# ESP_CAM_VVN_v5.net
KiCad netlist of a schematic drawn in EAGLE
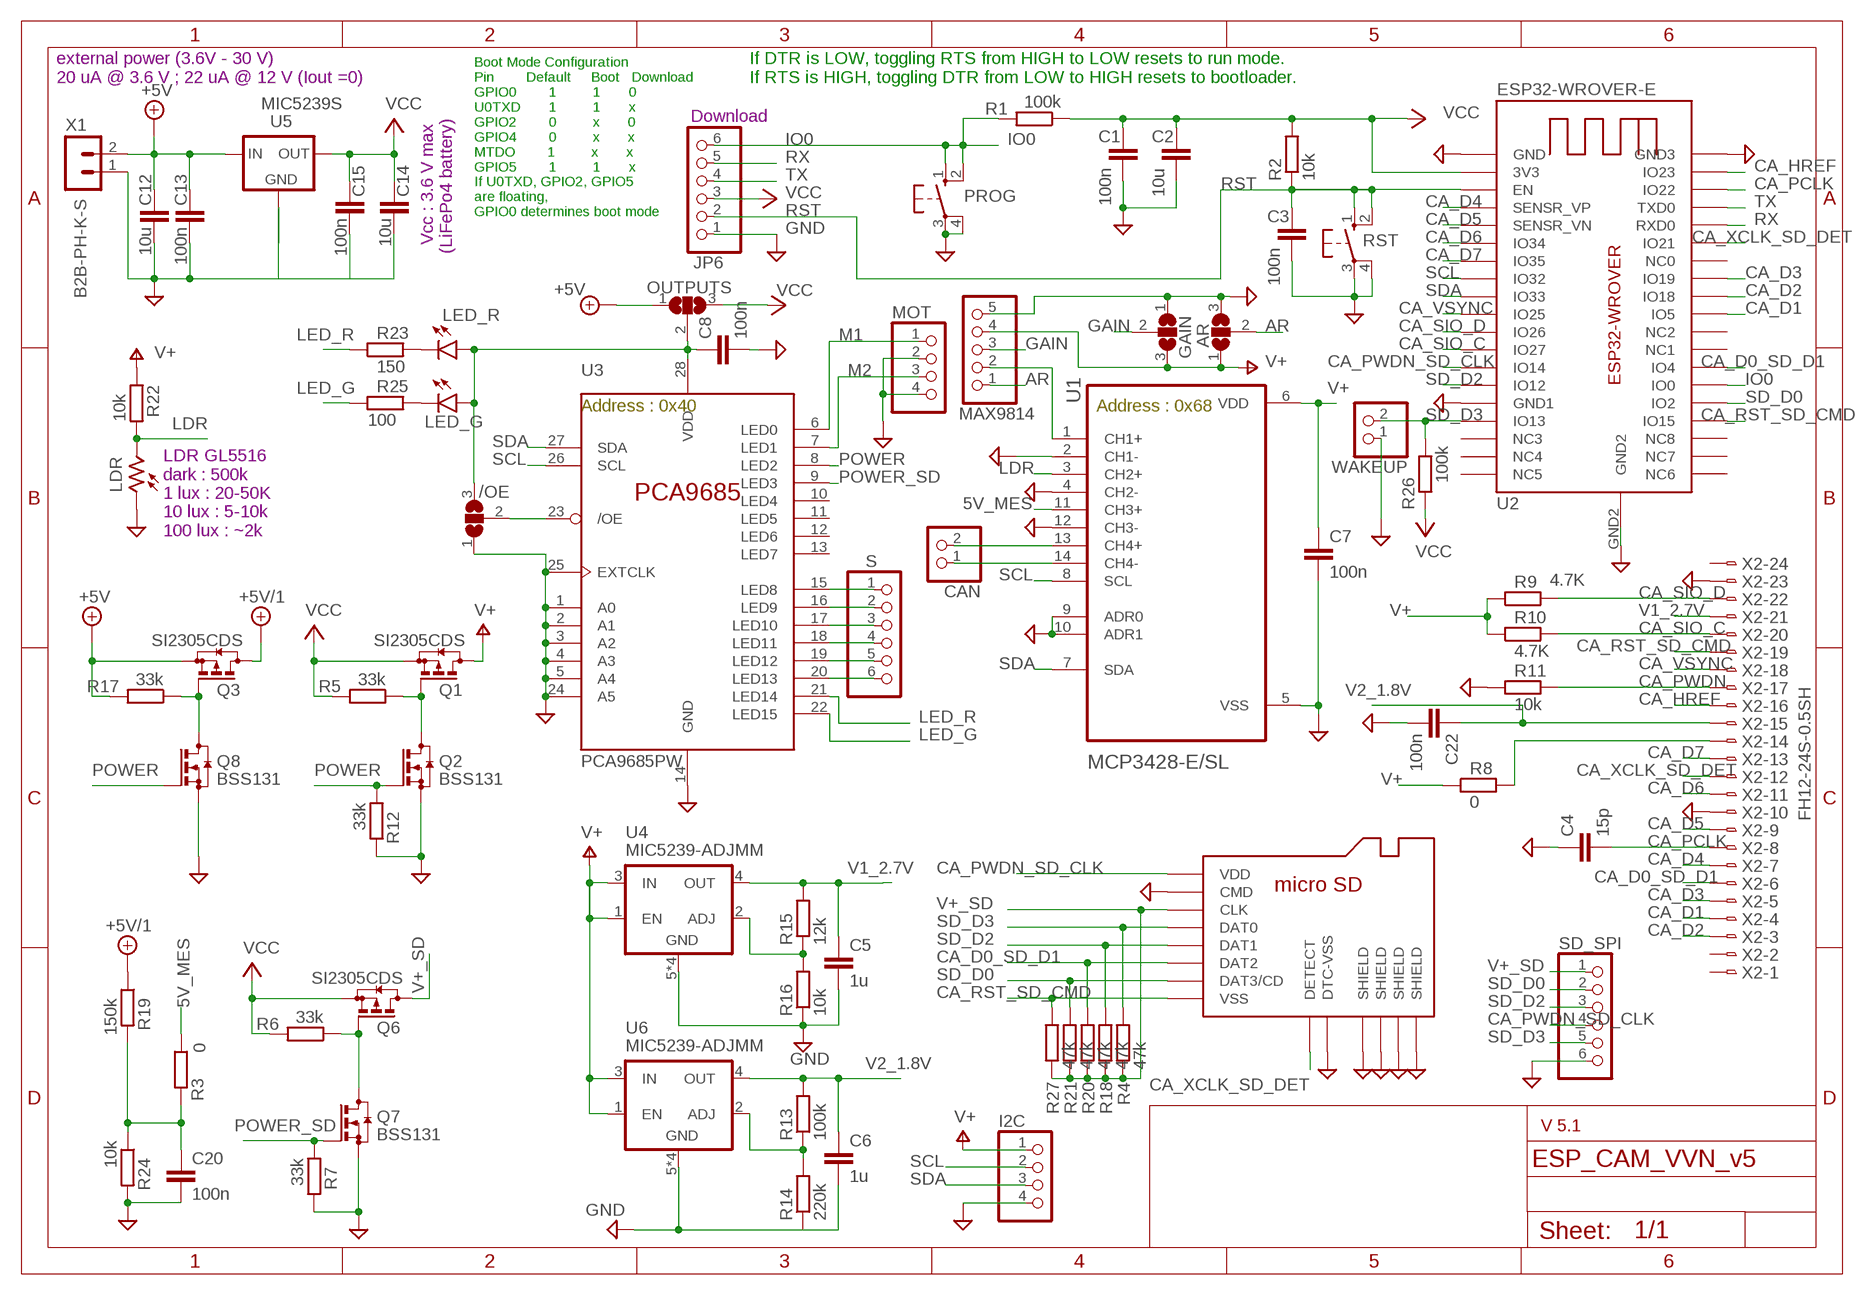
[diagram p0: schematic, sheet 1]

(export (version "E")
  (design (tool "Eeschema 10.0.6"))
  (components
    (comp (ref "/OE")
      (value "SJ2W")
      (footprint "eagle-import:SJ_2")
      (libsource (lib "eagle-import") (part "SJ2W"))
    )
    (comp (ref "AR")
      (value "SJ2W")
      (footprint "eagle-import:SJ_2")
      (libsource (lib "eagle-import") (part "SJ2W"))
    )
    (comp (ref "C1")
      (value "100n")
      (footprint "eagle-import:C1206")
      (libsource (lib "eagle-import") (part "CC1206"))
    )
    (comp (ref "C2")
      (value "10u")
      (footprint "eagle-import:C1206")
      (libsource (lib "eagle-import") (part "CC1206"))
    )
    (comp (ref "C3")
      (value "100n")
      (footprint "eagle-import:C1206")
      (libsource (lib "eagle-import") (part "CC1206"))
    )
    (comp (ref "C4")
      (value "15p")
      (footprint "eagle-import:C1206")
      (libsource (lib "eagle-import") (part "CC1206"))
    )
    (comp (ref "C5")
      (value "1u")
      (footprint "eagle-import:C1206")
      (libsource (lib "eagle-import") (part "C-EUC1206"))
    )
    (comp (ref "C6")
      (value "1u")
      (footprint "eagle-import:C1206")
      (libsource (lib "eagle-import") (part "C-EUC1206"))
    )
    (comp (ref "C7")
      (value "100n")
      (footprint "eagle-import:C1206")
      (libsource (lib "eagle-import") (part "CC1206"))
    )
    (comp (ref "C8")
      (value "100n")
      (footprint "eagle-import:C1206")
      (libsource (lib "eagle-import") (part "CC1206"))
    )
    (comp (ref "C12")
      (value "10u")
      (footprint "eagle-import:C1206")
      (libsource (lib "eagle-import") (part "CC1206"))
    )
    (comp (ref "C13")
      (value "100n")
      (footprint "eagle-import:C1206")
      (libsource (lib "eagle-import") (part "CC1206"))
    )
    (comp (ref "C14")
      (value "10u")
      (footprint "eagle-import:C1206")
      (libsource (lib "eagle-import") (part "CC1206"))
    )
    (comp (ref "C15")
      (value "100n")
      (footprint "eagle-import:C1206")
      (libsource (lib "eagle-import") (part "CC1206"))
    )
    (comp (ref "C20")
      (value "100n")
      (footprint "eagle-import:C1206")
      (libsource (lib "eagle-import") (part "CC1206"))
    )
    (comp (ref "C22")
      (value "100n")
      (footprint "eagle-import:C1206")
      (libsource (lib "eagle-import") (part "CC1206"))
    )
    (comp (ref "CAN")
      (value "PINHD-1X2")
      (footprint "eagle-import:1X02")
      (libsource (lib "eagle-import") (part "PINHD-1X2"))
    )
    (comp (ref "GAIN")
      (value "SJ2W")
      (footprint "eagle-import:SJ_2")
      (libsource (lib "eagle-import") (part "SJ2W"))
    )
    (comp (ref "I2C")
      (value "PINHD-1X4")
      (footprint "eagle-import:1X04")
      (libsource (lib "eagle-import") (part "PINHD-1X4"))
    )
    (comp (ref "JP6")
      (value "PINHD-1X6/90")
      (footprint "eagle-import:1X06_90")
      (libsource (lib "eagle-import") (part "PINHD-1X6/90"))
    )
    (comp (ref "LDR")
      (value "VT93N2")
      (footprint "eagle-import:VT900")
      (libsource (lib "eagle-import") (part "VT93N2"))
    )
    (comp (ref "LED_G")
      (value "LEDSMT1206")
      (footprint "eagle-import:1206")
      (libsource (lib "eagle-import") (part "LEDSMT1206"))
    )
    (comp (ref "LED_R")
      (value "LEDSMT1206")
      (footprint "eagle-import:1206")
      (libsource (lib "eagle-import") (part "LEDSMT1206"))
    )
    (comp (ref "MAX9814")
      (value "PINHD-1X5")
      (footprint "eagle-import:1X05")
      (libsource (lib "eagle-import") (part "PINHD-1X5"))
    )
    (comp (ref "MOT")
      (value "PINHD-1X4")
      (footprint "eagle-import:1X04")
      (libsource (lib "eagle-import") (part "PINHD-1X4"))
    )
    (comp (ref "OUTPUTS")
      (value "SJ2W")
      (footprint "eagle-import:SJ_2")
      (libsource (lib "eagle-import") (part "SJ2W"))
    )
    (comp (ref "PROG")
      (value "10-XX")
      (footprint "eagle-import:B3F-10XX")
      (fields (field (name "MPN") "B3F-1000"))
      (libsource (lib "eagle-import") (part "10-XX"))
    )
    (comp (ref "Q1")
      (value "SI2305CDS")
      (footprint "eagle-import:SOT23")
      (libsource (lib "eagle-import") (part "SI2305CDS"))
    )
    (comp (ref "Q2")
      (value "BSS131")
      (footprint "eagle-import:SOT23")
      (libsource (lib "eagle-import") (part "BSS131"))
    )
    (comp (ref "Q3")
      (value "SI2305CDS")
      (footprint "eagle-import:SOT23")
      (libsource (lib "eagle-import") (part "SI2305CDS"))
    )
    (comp (ref "Q6")
      (value "SI2305CDS")
      (footprint "eagle-import:SOT23")
      (libsource (lib "eagle-import") (part "SI2305CDS"))
    )
    (comp (ref "Q7")
      (value "BSS131")
      (footprint "eagle-import:SOT23")
      (libsource (lib "eagle-import") (part "BSS131"))
    )
    (comp (ref "Q8")
      (value "BSS131")
      (footprint "eagle-import:SOT23")
      (libsource (lib "eagle-import") (part "BSS131"))
    )
    (comp (ref "R1")
      (value "100k")
      (footprint "eagle-import:R1206")
      (libsource (lib "eagle-import") (part "RR1206"))
    )
    (comp (ref "R2")
      (value "10k")
      (footprint "eagle-import:R1206")
      (libsource (lib "eagle-import") (part "RR1206"))
    )
    (comp (ref "R3")
      (value "0")
      (footprint "eagle-import:R1206")
      (libsource (lib "eagle-import") (part "RR1206"))
    )
    (comp (ref "R4")
      (value "47k")
      (footprint "eagle-import:R0805")
      (libsource (lib "eagle-import") (part "R-EU_R0805"))
    )
    (comp (ref "R5")
      (value "33k")
      (footprint "eagle-import:R1206")
      (libsource (lib "eagle-import") (part "RR1206"))
    )
    (comp (ref "R6")
      (value "33k")
      (footprint "eagle-import:R1206")
      (libsource (lib "eagle-import") (part "RR1206"))
    )
    (comp (ref "R7")
      (value "33k")
      (footprint "eagle-import:R1206")
      (libsource (lib "eagle-import") (part "RR1206"))
    )
    (comp (ref "R8")
      (value "0")
      (footprint "eagle-import:R1206")
      (libsource (lib "eagle-import") (part "RR1206"))
    )
    (comp (ref "R9")
      (value "4.7K")
      (footprint "eagle-import:R1206")
      (libsource (lib "eagle-import") (part "RR1206"))
    )
    (comp (ref "R10")
      (value "4.7K")
      (footprint "eagle-import:R1206")
      (libsource (lib "eagle-import") (part "RR1206"))
    )
    (comp (ref "R11")
      (value "10k")
      (footprint "eagle-import:R1206")
      (libsource (lib "eagle-import") (part "RR1206"))
    )
    (comp (ref "R12")
      (value "33k")
      (footprint "eagle-import:R1206")
      (libsource (lib "eagle-import") (part "RR1206"))
    )
    (comp (ref "R13")
      (value "100k")
      (footprint "eagle-import:R1206")
      (libsource (lib "eagle-import") (part "R-EU_R1206"))
    )
    (comp (ref "R14")
      (value "220k")
      (footprint "eagle-import:R1206")
      (libsource (lib "eagle-import") (part "R-EU_R1206"))
    )
    (comp (ref "R15")
      (value "12k")
      (footprint "eagle-import:R1206")
      (libsource (lib "eagle-import") (part "R-EU_R1206"))
    )
    (comp (ref "R16")
      (value "10k")
      (footprint "eagle-import:R1206")
      (libsource (lib "eagle-import") (part "R-EU_R1206"))
    )
    (comp (ref "R17")
      (value "33k")
      (footprint "eagle-import:R1206")
      (libsource (lib "eagle-import") (part "RR1206"))
    )
    (comp (ref "R18")
      (value "47k")
      (footprint "eagle-import:R0805")
      (libsource (lib "eagle-import") (part "R-EU_R0805"))
    )
    (comp (ref "R19")
      (value "150k")
      (footprint "eagle-import:R1206")
      (libsource (lib "eagle-import") (part "RR1206"))
    )
    (comp (ref "R20")
      (value "47k")
      (footprint "eagle-import:R0805")
      (libsource (lib "eagle-import") (part "R-EU_R0805"))
    )
    (comp (ref "R21")
      (value "47k")
      (footprint "eagle-import:R0805")
      (libsource (lib "eagle-import") (part "R-EU_R0805"))
    )
    (comp (ref "R22")
      (value "10k")
      (footprint "eagle-import:R1206")
      (libsource (lib "eagle-import") (part "RR1206"))
    )
    (comp (ref "R23")
      (value "150")
      (footprint "eagle-import:R1206")
      (libsource (lib "eagle-import") (part "RR1206"))
    )
    (comp (ref "R24")
      (value "10k")
      (footprint "eagle-import:R1206")
      (libsource (lib "eagle-import") (part "RR1206"))
    )
    (comp (ref "R25")
      (value "100")
      (footprint "eagle-import:R1206")
      (libsource (lib "eagle-import") (part "RR1206"))
    )
    (comp (ref "R26")
      (value "100k")
      (footprint "eagle-import:R1206")
      (libsource (lib "eagle-import") (part "RR1206"))
    )
    (comp (ref "R27")
      (value "47k")
      (footprint "eagle-import:R0805")
      (libsource (lib "eagle-import") (part "R-EU_R0805"))
    )
    (comp (ref "RST")
      (value "10-XX")
      (footprint "eagle-import:B3F-10XX")
      (fields (field (name "MPN") "B3F-1000"))
      (libsource (lib "eagle-import") (part "10-XX"))
    )
    (comp (ref "S")
      (value "PINHD-1X6")
      (footprint "eagle-import:1X06")
      (libsource (lib "eagle-import") (part "PINHD-1X6"))
    )
    (comp (ref "SD1")
      (value "MICRO-SD-8")
      (footprint "eagle-import:MICROSDMOLEX")
      (libsource (lib "eagle-import") (part "MICRO-SD-8"))
    )
    (comp (ref "SD_SPI")
      (value "PINHD-1X6")
      (footprint "eagle-import:1X06")
      (libsource (lib "eagle-import") (part "PINHD-1X6"))
    )
    (comp (ref "U1")
      (value "MCP3428-E/SL")
      (footprint "eagle-import:SOIC127P600X175-14N")
      (fields (field (name "MF") "Microchip"))
      (libsource (lib "eagle-import") (part "MCP3428-E/SL"))
    )
    (comp (ref "U2")
      (value "ESP32-WROVER-E")
      (footprint "eagle-import:ESP32-WROVER")
      (libsource (lib "eagle-import") (part "ESP32-WROVER-E"))
    )
    (comp (ref "U3")
      (value "PCA9685PW")
      (footprint "eagle-import:TSSOP28")
      (libsource (lib "eagle-import") (part "PCA9685PW"))
    )
    (comp (ref "U4")
      (value "MIC5239-ADJMM")
      (footprint "eagle-import:MSOP08")
      (libsource (lib "eagle-import") (part "MIC5239-ADJMM"))
    )
    (comp (ref "U5")
      (value "MIC5239S")
      (footprint "eagle-import:SOT223")
      (libsource (lib "eagle-import") (part "MIC5239S"))
    )
    (comp (ref "U6")
      (value "MIC5239-ADJMM")
      (footprint "eagle-import:MSOP08")
      (libsource (lib "eagle-import") (part "MIC5239-ADJMM"))
    )
    (comp (ref "WAKEUP")
      (value "PINHD-1X2")
      (footprint "eagle-import:1X02")
      (libsource (lib "eagle-import") (part "PINHD-1X2"))
    )
    (comp (ref "X1")
      (value "B2B-PH-K-S")
      (footprint "eagle-import:B2B-PH-K-S")
      (libsource (lib "eagle-import") (part "B2B-PH-K-S"))
    )
    (comp (ref "X2")
      (value "FH12-24S-0.5SH")
      (footprint "eagle-import:FH12-24S-0.5SH")
      (fields (field (name "MPN") "FH12-24S-0.5SH(55)"))
      (libsource (lib "eagle-import") (part "FH12-24S-0.5SH"))
    )
  )
  (nets
    (net (code "1") (name "+5V") (class "Default")
      (node (ref "C12") (pin "1") (pinfunction "1_1") (pintype "passive"))
      (node (ref "C13") (pin "1") (pinfunction "1_1") (pintype "passive"))
      (node (ref "OUTPUTS") (pin "1") (pinfunction "1_1") (pintype "passive"))
      (node (ref "Q3") (pin "2") (pinfunction "S_2") (pintype "passive"))
      (node (ref "R17") (pin "2") (pinfunction "2_2") (pintype "passive"))
      (node (ref "U5") (pin "1") (pinfunction "IN_1") (pintype "input"))
      (node (ref "X1") (pin "2") (pinfunction "2_2") (pintype "passive"))
    )
    (net (code "2") (name "+5V{slash}1") (class "Default")
      (node (ref "Q3") (pin "3") (pinfunction "D_3") (pintype "passive"))
      (node (ref "R19") (pin "1") (pinfunction "1_1") (pintype "passive"))
    )
    (net (code "3") (name "/5V_MES") (class "Default")
      (node (ref "R3") (pin "1") (pinfunction "1_1") (pintype "passive"))
      (node (ref "U1") (pin "11") (pinfunction "CH3+_11") (pintype "input"))
    )
    (net (code "4") (name "/AR") (class "Default")
      (node (ref "AR") (pin "2") (pinfunction "2_2") (pintype "passive"))
      (node (ref "MAX9814") (pin "1") (pinfunction "1_1") (pintype "passive"))
    )
    (net (code "5") (name "/CA_D0_SD_D1") (class "Default")
      (node (ref "R20") (pin "2") (pinfunction "2_2") (pintype "passive"))
      (node (ref "SD1") (pin "P$1") (pinfunction "DAT2_P$1") (pintype "bidirectional"))
      (node (ref "U2") (pin "IO4") (pinfunction "IO4_IO4") (pintype "bidirectional"))
      (node (ref "X2") (pin "6") (pinfunction "1_6") (pintype "passive"))
    )
    (net (code "6") (name "/CA_D1") (class "Default")
      (node (ref "U2") (pin "IO5") (pinfunction "IO5_IO5") (pintype "bidirectional"))
      (node (ref "X2") (pin "4") (pinfunction "1_4") (pintype "passive"))
    )
    (net (code "7") (name "/CA_D2") (class "Default")
      (node (ref "U2") (pin "IO18") (pinfunction "IO18_IO18") (pintype "bidirectional"))
      (node (ref "X2") (pin "3") (pinfunction "1_3") (pintype "passive"))
    )
    (net (code "8") (name "/CA_D3") (class "Default")
      (node (ref "U2") (pin "IO19") (pinfunction "IO19_IO19") (pintype "bidirectional"))
      (node (ref "X2") (pin "5") (pinfunction "1_5") (pintype "passive"))
    )
    (net (code "9") (name "/CA_D4") (class "Default")
      (node (ref "U2") (pin "SENSOR_VP") (pinfunction "SENSR_VP_SENSOR_VP") (pintype "bidirectional"))
      (node (ref "X2") (pin "7") (pinfunction "1_7") (pintype "passive"))
    )
    (net (code "10") (name "/CA_D5") (class "Default")
      (node (ref "U2") (pin "SENSOR_VN") (pinfunction "SENSR_VN_SENSOR_VN") (pintype "bidirectional"))
      (node (ref "X2") (pin "9") (pinfunction "1_9") (pintype "passive"))
    )
    (net (code "11") (name "/CA_D6") (class "Default")
      (node (ref "U2") (pin "IO34") (pinfunction "IO34_IO34") (pintype "bidirectional"))
      (node (ref "X2") (pin "11") (pinfunction "1_11") (pintype "passive"))
    )
    (net (code "12") (name "/CA_D7") (class "Default")
      (node (ref "U2") (pin "IO35") (pinfunction "IO35_IO35") (pintype "bidirectional"))
      (node (ref "X2") (pin "13") (pinfunction "1_13") (pintype "passive"))
    )
    (net (code "13") (name "/CA_HREF") (class "Default")
      (node (ref "U2") (pin "IO23") (pinfunction "IO23_IO23") (pintype "bidirectional"))
      (node (ref "X2") (pin "16") (pinfunction "1_16") (pintype "passive"))
    )
    (net (code "14") (name "/CA_PCLK") (class "Default")
      (node (ref "C4") (pin "2") (pinfunction "2_2") (pintype "passive"))
      (node (ref "U2") (pin "IO22") (pinfunction "IO22_IO22") (pintype "bidirectional"))
      (node (ref "X2") (pin "8") (pinfunction "1_8") (pintype "passive"))
    )
    (net (code "15") (name "/CA_PWDN") (class "Default")
      (node (ref "R11") (pin "2") (pinfunction "2_2") (pintype "passive"))
      (node (ref "X2") (pin "17") (pinfunction "1_17") (pintype "passive"))
    )
    (net (code "16") (name "/CA_PWDN_SD_CLK") (class "Default")
      (node (ref "SD1") (pin "P$4") (pinfunction "VDD_P$4") (pintype "power_in"))
      (node (ref "SD_SPI") (pin "4") (pinfunction "4_4") (pintype "passive"))
      (node (ref "U2") (pin "IO14") (pinfunction "IO14_IO14") (pintype "bidirectional"))
    )
    (net (code "17") (name "/CA_RST_SD_CMD") (class "Default")
      (node (ref "R27") (pin "2") (pinfunction "2_2") (pintype "passive"))
      (node (ref "SD1") (pin "P$6") (pinfunction "VSS_P$6") (pintype "power_in"))
      (node (ref "U2") (pin "IO15") (pinfunction "IO15_IO15") (pintype "bidirectional"))
      (node (ref "X2") (pin "19") (pinfunction "1_19") (pintype "passive"))
    )
    (net (code "18") (name "/CA_SIO_C") (class "Default")
      (node (ref "R10") (pin "2") (pinfunction "2_2") (pintype "passive"))
      (node (ref "U2") (pin "IO27") (pinfunction "IO27_IO27") (pintype "bidirectional"))
      (node (ref "X2") (pin "20") (pinfunction "1_20") (pintype "passive"))
    )
    (net (code "19") (name "/CA_SIO_D") (class "Default")
      (node (ref "R9") (pin "2") (pinfunction "2_2") (pintype "passive"))
      (node (ref "U2") (pin "IO26") (pinfunction "IO26_IO26") (pintype "bidirectional"))
      (node (ref "X2") (pin "22") (pinfunction "1_22") (pintype "passive"))
    )
    (net (code "20") (name "/CA_VSYNC") (class "Default")
      (node (ref "U2") (pin "IO25") (pinfunction "IO25_IO25") (pintype "bidirectional"))
      (node (ref "X2") (pin "18") (pinfunction "1_18") (pintype "passive"))
    )
    (net (code "21") (name "/CA_XCLK_SD_DET") (class "Default")
      (node (ref "SD1") (pin "P$14") (pinfunction "DETECT_P$14") (pintype "power_in"))
      (node (ref "U2") (pin "IO21") (pinfunction "IO21_IO21") (pintype "bidirectional"))
      (node (ref "X2") (pin "12") (pinfunction "1_12") (pintype "passive"))
    )
    (net (code "22") (name "/GAIN") (class "Default")
      (node (ref "GAIN") (pin "2") (pinfunction "2_2") (pintype "passive"))
      (node (ref "MAX9814") (pin "3") (pinfunction "3_3") (pintype "passive"))
    )
    (net (code "23") (name "/IO0") (class "Default")
      (node (ref "JP6") (pin "6") (pinfunction "6_6") (pintype "passive"))
      (node (ref "PROG") (pin "1") (pinfunction "S_1") (pintype "passive"))
      (node (ref "PROG") (pin "2") (pinfunction "S1_2") (pintype "passive"))
      (node (ref "R1") (pin "2") (pinfunction "2_2") (pintype "passive"))
      (node (ref "U2") (pin "IO0") (pinfunction "IO0_IO0") (pintype "bidirectional"))
    )
    (net (code "24") (name "/LDR") (class "Default")
      (node (ref "LDR") (pin "2") (pinfunction "2_2") (pintype "passive"))
      (node (ref "R22") (pin "2") (pinfunction "2_2") (pintype "passive"))
      (node (ref "U1") (pin "3") (pinfunction "CH2+_3") (pintype "input"))
    )
    (net (code "25") (name "/LED_G") (class "Default")
      (node (ref "R25") (pin "1") (pinfunction "1_1") (pintype "passive"))
      (node (ref "U3") (pin "22") (pinfunction "LED15_22") (pintype "bidirectional"))
    )
    (net (code "26") (name "/LED_R") (class "Default")
      (node (ref "R23") (pin "1") (pinfunction "1_1") (pintype "passive"))
      (node (ref "U3") (pin "21") (pinfunction "LED14_21") (pintype "bidirectional"))
    )
    (net (code "27") (name "/M1") (class "Default")
      (node (ref "MOT") (pin "1") (pinfunction "1_1") (pintype "passive"))
      (node (ref "U3") (pin "6") (pinfunction "LED0_6") (pintype "bidirectional"))
    )
    (net (code "28") (name "/M2") (class "Default")
      (node (ref "MOT") (pin "3") (pinfunction "3_3") (pintype "passive"))
      (node (ref "U3") (pin "7") (pinfunction "LED1_7") (pintype "bidirectional"))
    )
    (net (code "29") (name "/POWER") (class "Default")
      (node (ref "Q2") (pin "1") (pinfunction "G_1") (pintype "passive"))
      (node (ref "Q8") (pin "1") (pinfunction "G_1") (pintype "passive"))
      (node (ref "R12") (pin "1") (pinfunction "1_1") (pintype "passive"))
      (node (ref "U3") (pin "8") (pinfunction "LED2_8") (pintype "bidirectional"))
    )
    (net (code "30") (name "/POWER_SD") (class "Default")
      (node (ref "Q7") (pin "1") (pinfunction "G_1") (pintype "passive"))
      (node (ref "R7") (pin "1") (pinfunction "1_1") (pintype "passive"))
      (node (ref "U3") (pin "9") (pinfunction "LED3_9") (pintype "bidirectional"))
    )
    (net (code "31") (name "/RST") (class "Default")
      (node (ref "C3") (pin "1") (pinfunction "1_1") (pintype "passive"))
      (node (ref "JP6") (pin "2") (pinfunction "2_2") (pintype "passive"))
      (node (ref "R2") (pin "1") (pinfunction "1_1") (pintype "passive"))
      (node (ref "RST") (pin "1") (pinfunction "S_1") (pintype "passive"))
      (node (ref "RST") (pin "2") (pinfunction "S1_2") (pintype "passive"))
      (node (ref "U2") (pin "EN") (pinfunction "EN_EN") (pintype "bidirectional"))
    )
    (net (code "32") (name "/RX") (class "Default")
      (node (ref "JP6") (pin "5") (pinfunction "5_5") (pintype "passive"))
      (node (ref "U2") (pin "RXD0") (pinfunction "RXD0_RXD0") (pintype "bidirectional"))
    )
    (net (code "33") (name "/SCL") (class "Default")
      (node (ref "I2C") (pin "2") (pinfunction "2_2") (pintype "passive"))
      (node (ref "U1") (pin "8") (pinfunction "SCL_8") (pintype "input"))
      (node (ref "U2") (pin "IO32") (pinfunction "IO32_IO32") (pintype "bidirectional"))
      (node (ref "U3") (pin "26") (pinfunction "SCL_26") (pintype "bidirectional"))
    )
    (net (code "34") (name "/SDA") (class "Default")
      (node (ref "I2C") (pin "3") (pinfunction "3_3") (pintype "passive"))
      (node (ref "U1") (pin "7") (pinfunction "SDA_7") (pintype "bidirectional"))
      (node (ref "U2") (pin "IO33") (pinfunction "IO33_IO33") (pintype "bidirectional"))
      (node (ref "U3") (pin "27") (pinfunction "SDA_27") (pintype "bidirectional"))
    )
    (net (code "35") (name "/SD_D0") (class "Default")
      (node (ref "R21") (pin "2") (pinfunction "2_2") (pintype "passive"))
      (node (ref "SD1") (pin "P$2") (pinfunction "DAT3/CD_P$2") (pintype "bidirectional"))
      (node (ref "SD_SPI") (pin "2") (pinfunction "2_2") (pintype "passive"))
      (node (ref "U2") (pin "IO2") (pinfunction "IO2_IO2") (pintype "bidirectional"))
    )
    (net (code "36") (name "/SD_D2") (class "Default")
      (node (ref "R18") (pin "2") (pinfunction "2_2") (pintype "passive"))
      (node (ref "SD1") (pin "P$8") (pinfunction "DAT1_P$8") (pintype "bidirectional"))
      (node (ref "SD_SPI") (pin "3") (pinfunction "3_3") (pintype "passive"))
      (node (ref "U2") (pin "IO12") (pinfunction "IO12_IO12") (pintype "bidirectional"))
    )
    (net (code "37") (name "/SD_D3") (class "Default")
      (node (ref "R26") (pin "2") (pinfunction "2_2") (pintype "passive"))
      (node (ref "R4") (pin "2") (pinfunction "2_2") (pintype "passive"))
      (node (ref "SD1") (pin "P$7") (pinfunction "DAT0_P$7") (pintype "bidirectional"))
      (node (ref "SD_SPI") (pin "5") (pinfunction "5_5") (pintype "passive"))
      (node (ref "U2") (pin "IO13") (pinfunction "IO13_IO13") (pintype "bidirectional"))
      (node (ref "WAKEUP") (pin "2") (pinfunction "2_2") (pintype "passive"))
    )
    (net (code "38") (name "/TX") (class "Default")
      (node (ref "JP6") (pin "4") (pinfunction "4_4") (pintype "passive"))
      (node (ref "U2") (pin "TXD0") (pinfunction "TXD0_TXD0") (pintype "bidirectional"))
    )
    (net (code "39") (name "/V+_SD") (class "Default")
      (node (ref "Q6") (pin "3") (pinfunction "D_3") (pintype "passive"))
      (node (ref "R18") (pin "1") (pinfunction "1_1") (pintype "passive"))
      (node (ref "R20") (pin "1") (pinfunction "1_1") (pintype "passive"))
      (node (ref "R21") (pin "1") (pinfunction "1_1") (pintype "passive"))
      (node (ref "R27") (pin "1") (pinfunction "1_1") (pintype "passive"))
      (node (ref "R4") (pin "1") (pinfunction "1_1") (pintype "passive"))
      (node (ref "SD1") (pin "P$5") (pinfunction "CLK_P$5") (pintype "bidirectional"))
      (node (ref "SD_SPI") (pin "1") (pinfunction "1_1") (pintype "passive"))
    )
    (net (code "40") (name "/V1_2.7V") (class "Default")
      (node (ref "C5") (pin "1") (pinfunction "1_1") (pintype "passive"))
      (node (ref "R15") (pin "2") (pinfunction "2_2") (pintype "passive"))
      (node (ref "U4") (pin "4") (pinfunction "OUT_4") (pintype "passive"))
      (node (ref "X2") (pin "21") (pinfunction "1_21") (pintype "passive"))
    )
    (net (code "41") (name "/V2_1.8V") (class "Default")
      (node (ref "C22") (pin "1") (pinfunction "1_1") (pintype "passive"))
      (node (ref "C6") (pin "1") (pinfunction "1_1") (pintype "passive"))
      (node (ref "R13") (pin "2") (pinfunction "2_2") (pintype "passive"))
      (node (ref "U6") (pin "4") (pinfunction "OUT_4") (pintype "passive"))
      (node (ref "X2") (pin "15") (pinfunction "1_15") (pintype "passive"))
    )
    (net (code "42") (name "GND") (class "Default")
      (node (ref "/OE") (pin "1") (pinfunction "1_1") (pintype "passive"))
      (node (ref "AR") (pin "3") (pinfunction "3_3") (pintype "passive"))
      (node (ref "C1") (pin "2") (pinfunction "2_2") (pintype "passive"))
      (node (ref "C12") (pin "2") (pinfunction "2_2") (pintype "passive"))
      (node (ref "C13") (pin "2") (pinfunction "2_2") (pintype "passive"))
      (node (ref "C14") (pin "2") (pinfunction "2_2") (pintype "passive"))
      (node (ref "C15") (pin "2") (pinfunction "2_2") (pintype "passive"))
      (node (ref "C2") (pin "2") (pinfunction "2_2") (pintype "passive"))
      (node (ref "C20") (pin "2") (pinfunction "2_2") (pintype "passive"))
      (node (ref "C22") (pin "2") (pinfunction "2_2") (pintype "passive"))
      (node (ref "C3") (pin "2") (pinfunction "2_2") (pintype "passive"))
      (node (ref "C4") (pin "1") (pinfunction "1_1") (pintype "passive"))
      (node (ref "C5") (pin "2") (pinfunction "2_2") (pintype "passive"))
      (node (ref "C6") (pin "2") (pinfunction "2_2") (pintype "passive"))
      (node (ref "C7") (pin "2") (pinfunction "2_2") (pintype "passive"))
      (node (ref "C8") (pin "2") (pinfunction "2_2") (pintype "passive"))
      (node (ref "GAIN") (pin "1") (pinfunction "1_1") (pintype "passive"))
      (node (ref "I2C") (pin "4") (pinfunction "4_4") (pintype "passive"))
      (node (ref "JP6") (pin "1") (pinfunction "1_1") (pintype "passive"))
      (node (ref "LDR") (pin "1") (pinfunction "1_1") (pintype "passive"))
      (node (ref "MAX9814") (pin "5") (pinfunction "5_5") (pintype "passive"))
      (node (ref "MOT") (pin "2") (pinfunction "2_2") (pintype "passive"))
      (node (ref "MOT") (pin "4") (pinfunction "4_4") (pintype "passive"))
      (node (ref "PROG") (pin "3") (pinfunction "P_3") (pintype "passive"))
      (node (ref "PROG") (pin "4") (pinfunction "P1_4") (pintype "passive"))
      (node (ref "Q2") (pin "2") (pinfunction "S_2") (pintype "passive"))
      (node (ref "Q7") (pin "2") (pinfunction "S_2") (pintype "passive"))
      (node (ref "Q8") (pin "2") (pinfunction "S_2") (pintype "passive"))
      (node (ref "R11") (pin "1") (pinfunction "1_1") (pintype "passive"))
      (node (ref "R12") (pin "2") (pinfunction "2_2") (pintype "passive"))
      (node (ref "R14") (pin "1") (pinfunction "1_1") (pintype "passive"))
      (node (ref "R16") (pin "1") (pinfunction "1_1") (pintype "passive"))
      (node (ref "R24") (pin "2") (pinfunction "2_2") (pintype "passive"))
      (node (ref "R7") (pin "2") (pinfunction "2_2") (pintype "passive"))
      (node (ref "RST") (pin "3") (pinfunction "P_3") (pintype "passive"))
      (node (ref "RST") (pin "4") (pinfunction "P1_4") (pintype "passive"))
      (node (ref "SD1") (pin "P$10") (pinfunction "SHIELD_P$10") (pintype "power_in"))
      (node (ref "SD1") (pin "P$11") (pinfunction "SHIELD_P$11") (pintype "power_in"))
      (node (ref "SD1") (pin "P$12") (pinfunction "SHIELD_P$12") (pintype "power_in"))
      (node (ref "SD1") (pin "P$13") (pinfunction "DTC-VSS_P$13") (pintype "power_in"))
      (node (ref "SD1") (pin "P$3") (pinfunction "CMD_P$3") (pintype "bidirectional"))
      (node (ref "SD1") (pin "P$9") (pinfunction "SHIELD_P$9") (pintype "power_in"))
      (node (ref "SD_SPI") (pin "6") (pinfunction "6_6") (pintype "passive"))
      (node (ref "U1") (pin "10") (pinfunction "ADR1_10") (pintype "bidirectional"))
      (node (ref "U1") (pin "12") (pinfunction "CH3-_12") (pintype "input"))
      (node (ref "U1") (pin "2") (pinfunction "CH1-_2") (pintype "input"))
      (node (ref "U1") (pin "4") (pinfunction "CH2-_4") (pintype "input"))
      (node (ref "U1") (pin "5") (pinfunction "VSS_5") (pintype "power_in"))
      (node (ref "U1") (pin "9") (pinfunction "ADR0_9") (pintype "bidirectional"))
      (node (ref "U2") (pin "GND") (pinfunction "GND_GND") (pintype "bidirectional"))
      (node (ref "U2") (pin "GND1") (pinfunction "GND1_GND1") (pintype "bidirectional"))
      (node (ref "U2") (pin "GND2") (pinfunction "GND2_GND2") (pintype "bidirectional"))
      (node (ref "U2") (pin "GND3") (pinfunction "GND3_GND3") (pintype "bidirectional"))
      (node (ref "U3") (pin "1") (pinfunction "A0_1") (pintype "bidirectional"))
      (node (ref "U3") (pin "14") (pinfunction "GND_14") (pintype "power_in"))
      (node (ref "U3") (pin "2") (pinfunction "A1_2") (pintype "bidirectional"))
      (node (ref "U3") (pin "24") (pinfunction "A5_24") (pintype "bidirectional"))
      (node (ref "U3") (pin "25") (pinfunction "EXTCLK_25") (pintype "input"))
      (node (ref "U3") (pin "3") (pinfunction "A2_3") (pintype "bidirectional"))
      (node (ref "U3") (pin "4") (pinfunction "A3_4") (pintype "bidirectional"))
      (node (ref "U3") (pin "5") (pinfunction "A4_5") (pintype "bidirectional"))
      (node (ref "U4") (pin "5") (pinfunction "GND_5") (pintype "power_in"))
      (node (ref "U4") (pin "6") (pinfunction "GND_6") (pintype "power_in"))
      (node (ref "U4") (pin "7") (pinfunction "GND_7") (pintype "power_in"))
      (node (ref "U4") (pin "8") (pinfunction "GND_8") (pintype "power_in"))
      (node (ref "U5") (pin "2") (pinfunction "GND_2") (pintype "passive"))
      (node (ref "U5") (pin "4") (pinfunction "GND_4") (pintype "passive"))
      (node (ref "U6") (pin "5") (pinfunction "GND_5") (pintype "power_in"))
      (node (ref "U6") (pin "6") (pinfunction "GND_6") (pintype "power_in"))
      (node (ref "U6") (pin "7") (pinfunction "GND_7") (pintype "power_in"))
      (node (ref "U6") (pin "8") (pinfunction "GND_8") (pintype "power_in"))
      (node (ref "WAKEUP") (pin "1") (pinfunction "1_1") (pintype "passive"))
      (node (ref "X1") (pin "1") (pinfunction "1_1") (pintype "passive"))
      (node (ref "X2") (pin "10") (pinfunction "1_10") (pintype "passive"))
      (node (ref "X2") (pin "23") (pinfunction "1_23") (pintype "passive"))
    )
    (net (code "43") (name "Net-(C20-Pad1)") (class "Default")
      (node (ref "C20") (pin "1") (pinfunction "1_1") (pintype "passive"))
      (node (ref "R19") (pin "2") (pinfunction "2_2") (pintype "passive"))
      (node (ref "R24") (pin "1") (pinfunction "1_1") (pintype "passive"))
      (node (ref "R3") (pin "2") (pinfunction "2_2") (pintype "passive"))
    )
    (net (code "44") (name "Net-(LED_G-PadC)") (class "Default")
      (node (ref "LED_G") (pin "C") (pinfunction "C_C") (pintype "passive"))
      (node (ref "R25") (pin "2") (pinfunction "2_2") (pintype "passive"))
    )
    (net (code "45") (name "Net-(LED_R-PadC)") (class "Default")
      (node (ref "LED_R") (pin "C") (pinfunction "C_C") (pintype "passive"))
      (node (ref "R23") (pin "2") (pinfunction "2_2") (pintype "passive"))
    )
    (net (code "46") (name "Net-(Q1-G)") (class "Default")
      (node (ref "Q1") (pin "1") (pinfunction "G_1") (pintype "passive"))
      (node (ref "Q2") (pin "3") (pinfunction "D_3") (pintype "passive"))
      (node (ref "R5") (pin "1") (pinfunction "1_1") (pintype "passive"))
    )
    (net (code "47") (name "Net-(Q3-G)") (class "Default")
      (node (ref "Q3") (pin "1") (pinfunction "G_1") (pintype "passive"))
      (node (ref "Q8") (pin "3") (pinfunction "D_3") (pintype "passive"))
      (node (ref "R17") (pin "1") (pinfunction "1_1") (pintype "passive"))
    )
    (net (code "48") (name "Net-(Q6-G)") (class "Default")
      (node (ref "Q6") (pin "1") (pinfunction "G_1") (pintype "passive"))
      (node (ref "Q7") (pin "3") (pinfunction "D_3") (pintype "passive"))
      (node (ref "R6") (pin "1") (pinfunction "1_1") (pintype "passive"))
    )
    (net (code "49") (name "Net-(U1-CH1+)") (class "Default")
      (node (ref "MAX9814") (pin "2") (pinfunction "2_2") (pintype "passive"))
      (node (ref "U1") (pin "1") (pinfunction "CH1+_1") (pintype "input"))
    )
    (net (code "50") (name "Net-(U1-CH4+)") (class "Default")
      (node (ref "CAN") (pin "2") (pinfunction "2_2") (pintype "passive"))
      (node (ref "U1") (pin "13") (pinfunction "CH4+_13") (pintype "input"))
    )
    (net (code "51") (name "Net-(U1-CH4-)") (class "Default")
      (node (ref "CAN") (pin "1") (pinfunction "1_1") (pintype "passive"))
      (node (ref "U1") (pin "14") (pinfunction "CH4-_14") (pintype "input"))
    )
    (net (code "52") (name "Net-(U3-LED8)") (class "Default")
      (node (ref "S") (pin "1") (pinfunction "1_1") (pintype "passive"))
      (node (ref "U3") (pin "15") (pinfunction "LED8_15") (pintype "bidirectional"))
    )
    (net (code "53") (name "Net-(U3-LED9)") (class "Default")
      (node (ref "S") (pin "2") (pinfunction "2_2") (pintype "passive"))
      (node (ref "U3") (pin "16") (pinfunction "LED9_16") (pintype "bidirectional"))
    )
    (net (code "54") (name "Net-(U3-LED10)") (class "Default")
      (node (ref "S") (pin "3") (pinfunction "3_3") (pintype "passive"))
      (node (ref "U3") (pin "17") (pinfunction "LED10_17") (pintype "bidirectional"))
    )
    (net (code "55") (name "Net-(U3-LED11)") (class "Default")
      (node (ref "S") (pin "4") (pinfunction "4_4") (pintype "passive"))
      (node (ref "U3") (pin "18") (pinfunction "LED11_18") (pintype "bidirectional"))
    )
    (net (code "56") (name "Net-(U3-LED12)") (class "Default")
      (node (ref "S") (pin "5") (pinfunction "5_5") (pintype "passive"))
      (node (ref "U3") (pin "19") (pinfunction "LED12_19") (pintype "bidirectional"))
    )
    (net (code "57") (name "Net-(U3-LED13)") (class "Default")
      (node (ref "S") (pin "6") (pinfunction "6_6") (pintype "passive"))
      (node (ref "U3") (pin "20") (pinfunction "LED13_20") (pintype "bidirectional"))
    )
    (net (code "58") (name "Net-(U3-VDD)") (class "Default")
      (node (ref "/OE") (pin "3") (pinfunction "3_3") (pintype "passive"))
      (node (ref "C8") (pin "1") (pinfunction "1_1") (pintype "passive"))
      (node (ref "LED_G") (pin "A") (pinfunction "A_A") (pintype "passive"))
      (node (ref "LED_R") (pin "A") (pinfunction "A_A") (pintype "passive"))
      (node (ref "OUTPUTS") (pin "2") (pinfunction "2_2") (pintype "passive"))
      (node (ref "U3") (pin "28") (pinfunction "VDD_28") (pintype "power_in"))
    )
    (net (code "59") (name "Net-(U3-{slash}OE)") (class "Default")
      (node (ref "/OE") (pin "2") (pinfunction "2_2") (pintype "passive"))
      (node (ref "U3") (pin "23") (pinfunction "/OE_23") (pintype "bidirectional"))
    )
    (net (code "60") (name "Net-(U4-ADJ)") (class "Default")
      (node (ref "R15") (pin "1") (pinfunction "1_1") (pintype "passive"))
      (node (ref "R16") (pin "2") (pinfunction "2_2") (pintype "passive"))
      (node (ref "U4") (pin "2") (pinfunction "ADJ_2") (pintype "passive"))
    )
    (net (code "61") (name "Net-(U6-ADJ)") (class "Default")
      (node (ref "R13") (pin "1") (pinfunction "1_1") (pintype "passive"))
      (node (ref "R14") (pin "2") (pinfunction "2_2") (pintype "passive"))
      (node (ref "U6") (pin "2") (pinfunction "ADJ_2") (pintype "passive"))
    )
    (net (code "62") (name "Net-(X2F-1)") (class "Default")
      (node (ref "R8") (pin "2") (pinfunction "2_2") (pintype "passive"))
      (node (ref "X2") (pin "14") (pinfunction "1_14") (pintype "passive"))
    )
    (net (code "63") (name "V+") (class "Default")
      (node (ref "AR") (pin "1") (pinfunction "1_1") (pintype "passive"))
      (node (ref "C7") (pin "1") (pinfunction "1_1") (pintype "passive"))
      (node (ref "GAIN") (pin "3") (pinfunction "3_3") (pintype "passive"))
      (node (ref "I2C") (pin "1") (pinfunction "1_1") (pintype "passive"))
      (node (ref "MAX9814") (pin "4") (pinfunction "4_4") (pintype "passive"))
      (node (ref "Q1") (pin "3") (pinfunction "D_3") (pintype "passive"))
      (node (ref "R10") (pin "1") (pinfunction "1_1") (pintype "passive"))
      (node (ref "R22") (pin "1") (pinfunction "1_1") (pintype "passive"))
      (node (ref "R8") (pin "1") (pinfunction "1_1") (pintype "passive"))
      (node (ref "R9") (pin "1") (pinfunction "1_1") (pintype "passive"))
      (node (ref "U1") (pin "6") (pinfunction "VDD_6") (pintype "power_in"))
      (node (ref "U4") (pin "1") (pinfunction "EN_1") (pintype "input"))
      (node (ref "U4") (pin "3") (pinfunction "IN_3") (pintype "input"))
      (node (ref "U6") (pin "1") (pinfunction "EN_1") (pintype "input"))
      (node (ref "U6") (pin "3") (pinfunction "IN_3") (pintype "input"))
    )
    (net (code "64") (name "VCC") (class "Default")
      (node (ref "C1") (pin "1") (pinfunction "1_1") (pintype "passive"))
      (node (ref "C14") (pin "1") (pinfunction "1_1") (pintype "passive"))
      (node (ref "C15") (pin "1") (pinfunction "1_1") (pintype "passive"))
      (node (ref "C2") (pin "1") (pinfunction "1_1") (pintype "passive"))
      (node (ref "JP6") (pin "3") (pinfunction "3_3") (pintype "passive"))
      (node (ref "OUTPUTS") (pin "3") (pinfunction "3_3") (pintype "passive"))
      (node (ref "Q1") (pin "2") (pinfunction "S_2") (pintype "passive"))
      (node (ref "Q6") (pin "2") (pinfunction "S_2") (pintype "passive"))
      (node (ref "R1") (pin "1") (pinfunction "1_1") (pintype "passive"))
      (node (ref "R2") (pin "2") (pinfunction "2_2") (pintype "passive"))
      (node (ref "R26") (pin "1") (pinfunction "1_1") (pintype "passive"))
      (node (ref "R5") (pin "2") (pinfunction "2_2") (pintype "passive"))
      (node (ref "R6") (pin "2") (pinfunction "2_2") (pintype "passive"))
      (node (ref "U2") (pin "VDD33") (pinfunction "3V3_VDD33") (pintype "bidirectional"))
      (node (ref "U5") (pin "3") (pinfunction "OUT_3") (pintype "passive"))
    )
    (net (code "65") (name "unconnected-(U2-NC3-PadCLK)") (class "Default")
      (node (ref "U2") (pin "CLK") (pinfunction "NC3_CLK") (pintype "bidirectional"))
    )
    (net (code "66") (name "unconnected-(U2-NC4-PadCMD)") (class "Default")
      (node (ref "U2") (pin "CMD") (pinfunction "NC4_CMD") (pintype "bidirectional"))
    )
    (net (code "67") (name "unconnected-(U2-NC5-PadSD0)") (class "Default")
      (node (ref "U2") (pin "SD0") (pinfunction "NC5_SD0") (pintype "bidirectional"))
    )
    (net (code "68") (name "unconnected-(U2-NC6-PadSD1)") (class "Default")
      (node (ref "U2") (pin "SD1") (pinfunction "NC6_SD1") (pintype "bidirectional"))
    )
    (net (code "69") (name "unconnected-(U2-NC7-PadSD2)") (class "Default")
      (node (ref "U2") (pin "SD2") (pinfunction "NC7_SD2") (pintype "bidirectional"))
    )
    (net (code "70") (name "unconnected-(U2-NC8-PadSD3)") (class "Default")
      (node (ref "U2") (pin "SD3") (pinfunction "NC8_SD3") (pintype "bidirectional"))
    )
    (net (code "71") (name "unconnected-(U2-PadNC0)") (class "Default")
      (node (ref "U2") (pin "NC0") (pinfunction "NC0_NC0") (pintype "bidirectional"))
    )
    (net (code "72") (name "unconnected-(U2-PadNC1)") (class "Default")
      (node (ref "U2") (pin "NC1") (pinfunction "NC1_NC1") (pintype "bidirectional"))
    )
    (net (code "73") (name "unconnected-(U2-PadNC2)") (class "Default")
      (node (ref "U2") (pin "NC2") (pinfunction "NC2_NC2") (pintype "bidirectional"))
    )
    (net (code "74") (name "unconnected-(U3-LED4-Pad10)") (class "Default")
      (node (ref "U3") (pin "10") (pinfunction "LED4_10") (pintype "bidirectional"))
    )
    (net (code "75") (name "unconnected-(U3-LED5-Pad11)") (class "Default")
      (node (ref "U3") (pin "11") (pinfunction "LED5_11") (pintype "bidirectional"))
    )
    (net (code "76") (name "unconnected-(U3-LED6-Pad12)") (class "Default")
      (node (ref "U3") (pin "12") (pinfunction "LED6_12") (pintype "bidirectional"))
    )
    (net (code "77") (name "unconnected-(U3-LED7-Pad13)") (class "Default")
      (node (ref "U3") (pin "13") (pinfunction "LED7_13") (pintype "bidirectional"))
    )
    (net (code "78") (name "unconnected-(X2-Pad1)") (class "Default")
      (node (ref "X2") (pin "1") (pinfunction "1_1") (pintype "passive"))
    )
    (net (code "79") (name "unconnected-(X2L-1-Pad2)") (class "Default")
      (node (ref "X2") (pin "2") (pinfunction "1_2") (pintype "passive"))
    )
    (net (code "80") (name "unconnected-(X2Q-1-Pad24)") (class "Default")
      (node (ref "X2") (pin "24") (pinfunction "1_24") (pintype "passive"))
    )
  )
)
